# teensy_mother_board.net
KiCad netlist of a schematic drawn in EAGLE
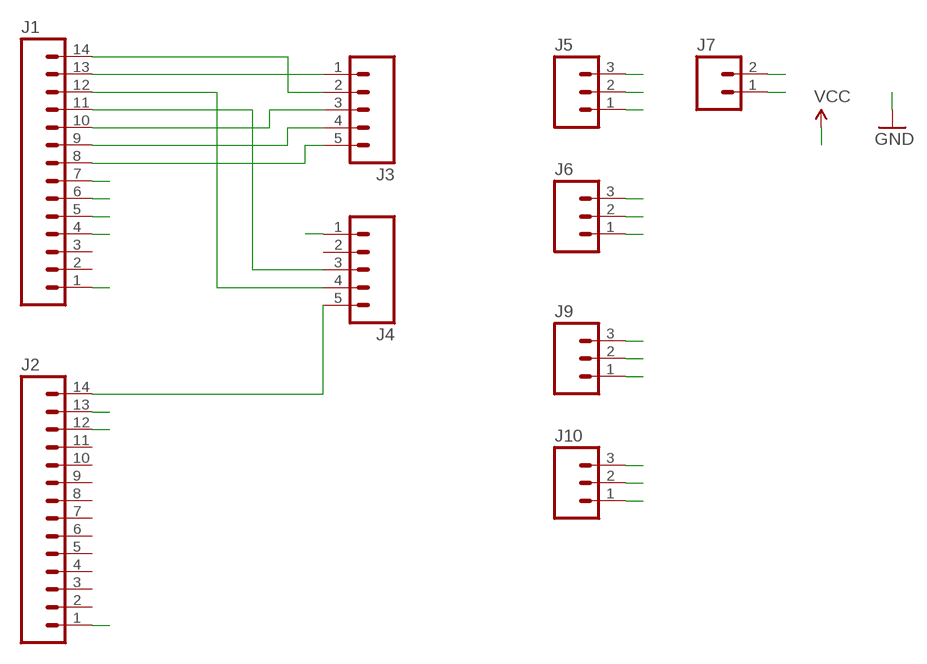
[diagram p0: schematic, sheet 1]

(export (version "E")
  (design (tool "Eeschema 10.0.6"))
  (components
    (comp (ref "J1")
      (value "M14")
      (footprint "eagle-import:1X14")
      (libsource (lib "eagle-import") (part "M14"))
    )
    (comp (ref "J2")
      (value "M14")
      (footprint "eagle-import:1X14")
      (libsource (lib "eagle-import") (part "M14"))
    )
    (comp (ref "J3")
      (value "M05PTH")
      (footprint "eagle-import:1X05")
      (libsource (lib "eagle-import") (part "M05PTH"))
    )
    (comp (ref "J4")
      (value "M05PTH")
      (footprint "eagle-import:1X05")
      (libsource (lib "eagle-import") (part "M05PTH"))
    )
    (comp (ref "J5")
      (value "M03PTH")
      (footprint "eagle-import:1X03")
      (libsource (lib "eagle-import") (part "M03PTH"))
    )
    (comp (ref "J6")
      (value "M03PTH")
      (footprint "eagle-import:1X03")
      (libsource (lib "eagle-import") (part "M03PTH"))
    )
    (comp (ref "J7")
      (value "M02JST-PTH-VERT")
      (footprint "eagle-import:JST-2-PTH-VERT")
      (libsource (lib "eagle-import") (part "M02JST-PTH-VERT"))
    )
    (comp (ref "J9")
      (value "M03PTH")
      (footprint "eagle-import:1X03")
      (libsource (lib "eagle-import") (part "M03PTH"))
    )
    (comp (ref "J10")
      (value "M03PTH")
      (footprint "eagle-import:1X03")
      (libsource (lib "eagle-import") (part "M03PTH"))
    )
  )
  (nets
    (net (code "1") (name "/MASTER_MUX1_IN") (class "Default")
      (node (ref "J2") (pin "13") (pinfunction "13_13") (pintype "passive"))
      (node (ref "J5") (pin "2") (pinfunction "2_2") (pintype "passive"))
    )
    (net (code "2") (name "/MASTER_MUX2_IN") (class "Default")
      (node (ref "J2") (pin "12") (pinfunction "12_12") (pintype "passive"))
      (node (ref "J9") (pin "2") (pinfunction "2_2") (pintype "passive"))
    )
    (net (code "3") (name "/MASTER_MUX_A") (class "Default")
      (node (ref "J1") (pin "7") (pinfunction "7_7") (pintype "passive"))
      (node (ref "J5") (pin "1") (pinfunction "1_1") (pintype "passive"))
      (node (ref "J9") (pin "1") (pinfunction "1_1") (pintype "passive"))
    )
    (net (code "4") (name "/MASTER_MUX_B") (class "Default")
      (node (ref "J1") (pin "6") (pinfunction "6_6") (pintype "passive"))
      (node (ref "J10") (pin "1") (pinfunction "1_1") (pintype "passive"))
      (node (ref "J6") (pin "1") (pinfunction "1_1") (pintype "passive"))
    )
    (net (code "5") (name "/MASTER_MUX_C") (class "Default")
      (node (ref "J1") (pin "5") (pinfunction "5_5") (pintype "passive"))
      (node (ref "J10") (pin "3") (pinfunction "3_3") (pintype "passive"))
      (node (ref "J6") (pin "3") (pinfunction "3_3") (pintype "passive"))
    )
    (net (code "6") (name "/MASTER_MUX_D") (class "Default")
      (node (ref "J1") (pin "4") (pinfunction "4_4") (pintype "passive"))
      (node (ref "J5") (pin "3") (pinfunction "3_3") (pintype "passive"))
      (node (ref "J9") (pin "3") (pinfunction "3_3") (pintype "passive"))
    )
    (net (code "7") (name "GND") (class "Default")
      (node (ref "J1") (pin "1") (pinfunction "1_1") (pintype "passive"))
      (node (ref "J10") (pin "2") (pinfunction "2_2") (pintype "passive"))
      (node (ref "J4") (pin "1") (pinfunction "1_1") (pintype "passive"))
      (node (ref "J6") (pin "2") (pinfunction "2_2") (pintype "passive"))
      (node (ref "J7") (pin "1") (pinfunction "1_1") (pintype "passive"))
    )
    (net (code "8") (name "Net-(J1-Pad8)") (class "Default")
      (node (ref "J1") (pin "8") (pinfunction "8_8") (pintype "passive"))
      (node (ref "J3") (pin "5") (pinfunction "5_5") (pintype "passive"))
    )
    (net (code "9") (name "Net-(J1-Pad9)") (class "Default")
      (node (ref "J1") (pin "9") (pinfunction "9_9") (pintype "passive"))
      (node (ref "J3") (pin "4") (pinfunction "4_4") (pintype "passive"))
    )
    (net (code "10") (name "Net-(J1-Pad10)") (class "Default")
      (node (ref "J1") (pin "10") (pinfunction "10_10") (pintype "passive"))
      (node (ref "J3") (pin "3") (pinfunction "3_3") (pintype "passive"))
    )
    (net (code "11") (name "Net-(J1-Pad11)") (class "Default")
      (node (ref "J1") (pin "11") (pinfunction "11_11") (pintype "passive"))
      (node (ref "J4") (pin "3") (pinfunction "3_3") (pintype "passive"))
    )
    (net (code "12") (name "Net-(J1-Pad12)") (class "Default")
      (node (ref "J1") (pin "12") (pinfunction "12_12") (pintype "passive"))
      (node (ref "J4") (pin "4") (pinfunction "4_4") (pintype "passive"))
    )
    (net (code "13") (name "Net-(J1-Pad13)") (class "Default")
      (node (ref "J1") (pin "13") (pinfunction "13_13") (pintype "passive"))
      (node (ref "J3") (pin "1") (pinfunction "1_1") (pintype "passive"))
    )
    (net (code "14") (name "Net-(J1-Pad14)") (class "Default")
      (node (ref "J1") (pin "14") (pinfunction "14_14") (pintype "passive"))
      (node (ref "J3") (pin "2") (pinfunction "2_2") (pintype "passive"))
    )
    (net (code "15") (name "Net-(J2-Pad14)") (class "Default")
      (node (ref "J2") (pin "14") (pinfunction "14_14") (pintype "passive"))
      (node (ref "J4") (pin "5") (pinfunction "5_5") (pintype "passive"))
    )
    (net (code "16") (name "VCC") (class "Default")
      (node (ref "J2") (pin "1") (pinfunction "1_1") (pintype "passive"))
      (node (ref "J7") (pin "2") (pinfunction "2_2") (pintype "passive"))
    )
    (net (code "17") (name "unconnected-(J1-Pad2)") (class "Default")
      (node (ref "J1") (pin "2") (pinfunction "2_2") (pintype "passive"))
    )
    (net (code "18") (name "unconnected-(J1-Pad3)") (class "Default")
      (node (ref "J1") (pin "3") (pinfunction "3_3") (pintype "passive"))
    )
    (net (code "19") (name "unconnected-(J2-Pad2)") (class "Default")
      (node (ref "J2") (pin "2") (pinfunction "2_2") (pintype "passive"))
    )
    (net (code "20") (name "unconnected-(J2-Pad3)") (class "Default")
      (node (ref "J2") (pin "3") (pinfunction "3_3") (pintype "passive"))
    )
    (net (code "21") (name "unconnected-(J2-Pad4)") (class "Default")
      (node (ref "J2") (pin "4") (pinfunction "4_4") (pintype "passive"))
    )
    (net (code "22") (name "unconnected-(J2-Pad5)") (class "Default")
      (node (ref "J2") (pin "5") (pinfunction "5_5") (pintype "passive"))
    )
    (net (code "23") (name "unconnected-(J2-Pad6)") (class "Default")
      (node (ref "J2") (pin "6") (pinfunction "6_6") (pintype "passive"))
    )
    (net (code "24") (name "unconnected-(J2-Pad7)") (class "Default")
      (node (ref "J2") (pin "7") (pinfunction "7_7") (pintype "passive"))
    )
    (net (code "25") (name "unconnected-(J2-Pad8)") (class "Default")
      (node (ref "J2") (pin "8") (pinfunction "8_8") (pintype "passive"))
    )
    (net (code "26") (name "unconnected-(J2-Pad9)") (class "Default")
      (node (ref "J2") (pin "9") (pinfunction "9_9") (pintype "passive"))
    )
    (net (code "27") (name "unconnected-(J2-Pad10)") (class "Default")
      (node (ref "J2") (pin "10") (pinfunction "10_10") (pintype "passive"))
    )
    (net (code "28") (name "unconnected-(J2-Pad11)") (class "Default")
      (node (ref "J2") (pin "11") (pinfunction "11_11") (pintype "passive"))
    )
    (net (code "29") (name "unconnected-(J4-Pad2)") (class "Default")
      (node (ref "J4") (pin "2") (pinfunction "2_2") (pintype "passive"))
    )
  )
)
